# Group_G.net
KiCad netlist of a schematic drawn in EAGLE
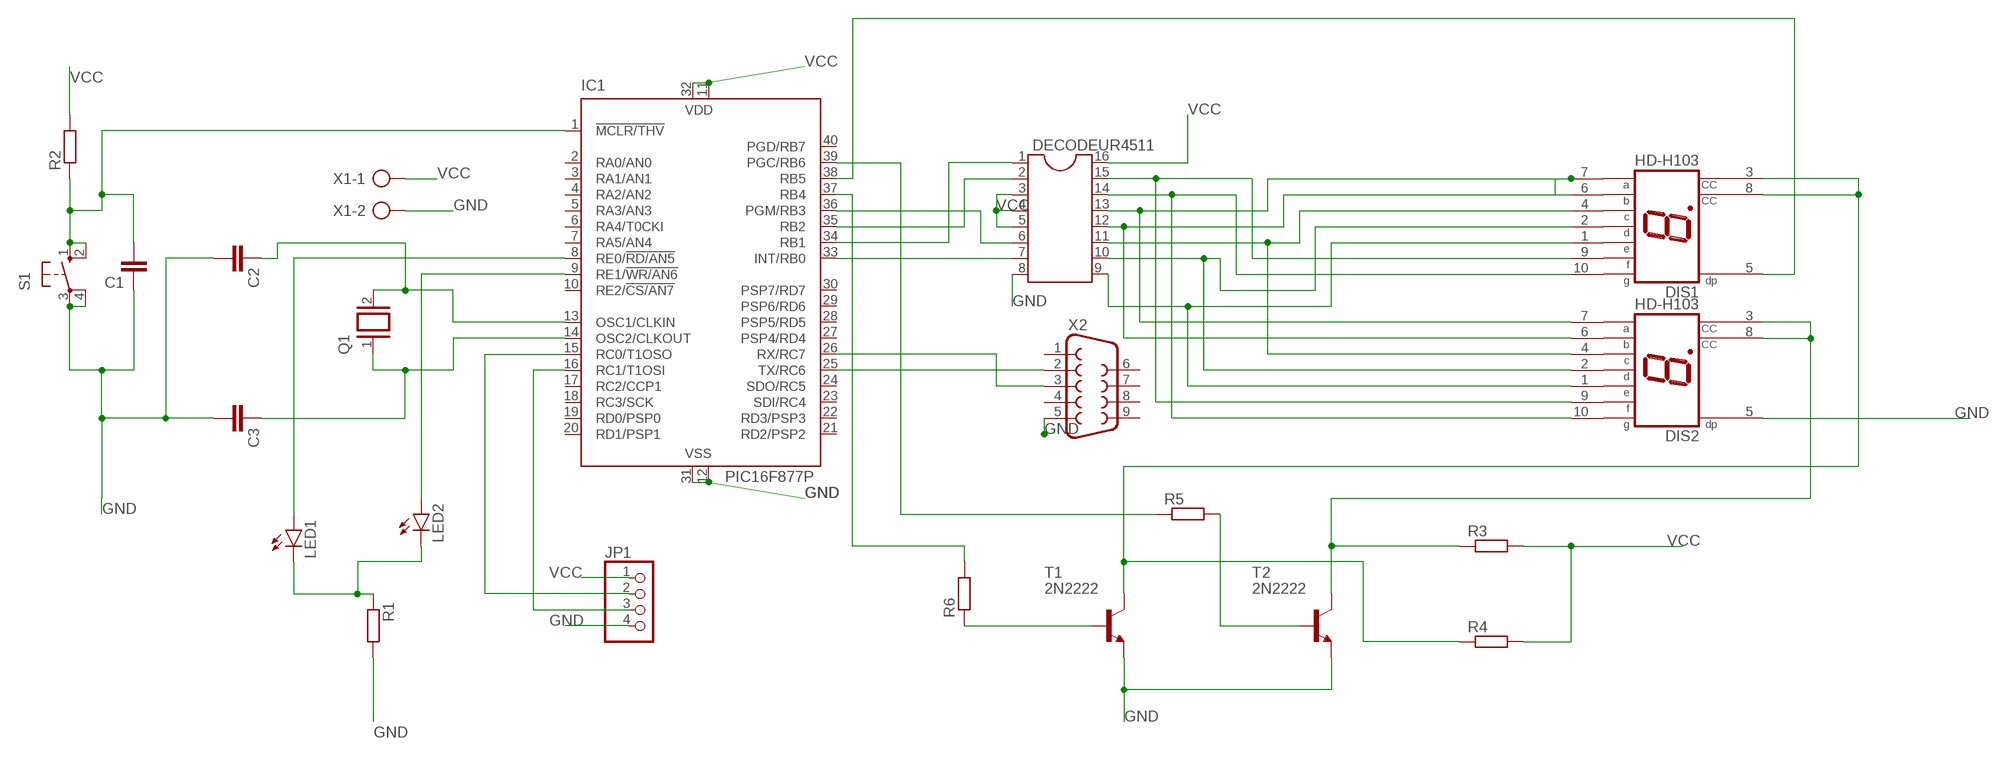
[diagram p0: schematic, sheet 1]

(export (version "E")
  (design (tool "Eeschema 10.0.6"))
  (components
    (comp (ref "C1")
      (value "C-EU025-025X050")
      (footprint "eagle-import:C025-025X050")
      (libsource (lib "eagle-import") (part "C-EU025-025X050"))
    )
    (comp (ref "C2")
      (value "C-EU025-025X050")
      (footprint "eagle-import:C025-025X050")
      (libsource (lib "eagle-import") (part "C-EU025-025X050"))
    )
    (comp (ref "C3")
      (value "C-EU025-025X050")
      (footprint "eagle-import:C025-025X050")
      (libsource (lib "eagle-import") (part "C-EU025-025X050"))
    )
    (comp (ref "DECODEUR4511")
      (value "DIL16")
      (footprint "eagle-import:DIL16")
      (libsource (lib "eagle-import") (part "DIL16"))
    )
    (comp (ref "DIS1")
      (value "HD-H103")
      (footprint "eagle-import:HDSP-M")
      (libsource (lib "eagle-import") (part "HD-H103"))
    )
    (comp (ref "DIS2")
      (value "HD-H103")
      (footprint "eagle-import:HDSP-M")
      (libsource (lib "eagle-import") (part "HD-H103"))
    )
    (comp (ref "IC1")
      (value "PIC16F877P")
      (footprint "eagle-import:DIL40")
      (fields (field (name "MF") "MICROCHIP") (field (name "MPN") "PIC16F877-04/P"))
      (libsource (lib "eagle-import") (part "PIC16F87P7"))
    )
    (comp (ref "JP1")
      (value "PINHD-1X4")
      (footprint "eagle-import:1X04")
      (libsource (lib "eagle-import") (part "PINHD-1X4"))
    )
    (comp (ref "LED1")
      (value "LED5MM")
      (footprint "eagle-import:LED5MM")
      (libsource (lib "eagle-import") (part "LED5MM"))
    )
    (comp (ref "LED2")
      (value "LED5MM")
      (footprint "eagle-import:LED5MM")
      (libsource (lib "eagle-import") (part "LED5MM"))
    )
    (comp (ref "Q1")
      (value "XTAL/S")
      (footprint "eagle-import:QS")
      (libsource (lib "eagle-import") (part "XTAL/S"))
    )
    (comp (ref "R1")
      (value "R-EU_0207/10")
      (footprint "eagle-import:0207_10")
      (libsource (lib "eagle-import") (part "R-EU_0207/10"))
    )
    (comp (ref "R2")
      (value "R-EU_0207/10")
      (footprint "eagle-import:0207_10")
      (libsource (lib "eagle-import") (part "R-EU_0207/10"))
    )
    (comp (ref "R3")
      (value "R-EU_0207/10")
      (footprint "eagle-import:0207_10")
      (libsource (lib "eagle-import") (part "R-EU_0207/10"))
    )
    (comp (ref "R4")
      (value "R-EU_0207/10")
      (footprint "eagle-import:0207_10")
      (libsource (lib "eagle-import") (part "R-EU_0207/10"))
    )
    (comp (ref "R5")
      (value "R-EU_0207/10")
      (footprint "eagle-import:0207_10")
      (libsource (lib "eagle-import") (part "R-EU_0207/10"))
    )
    (comp (ref "R6")
      (value "R-EU_0207/10")
      (footprint "eagle-import:0207_10")
      (libsource (lib "eagle-import") (part "R-EU_0207/10"))
    )
    (comp (ref "S1")
      (value "10-XX")
      (footprint "eagle-import:B3F-10XX")
      (fields (field (name "MPN") "B3F-1000"))
      (libsource (lib "eagle-import") (part "10-XX"))
    )
    (comp (ref "T1")
      (value "2N2222")
      (footprint "eagle-import:TO18")
      (libsource (lib "eagle-import") (part "2N2222"))
    )
    (comp (ref "T2")
      (value "2N2222")
      (footprint "eagle-import:TO18")
      (libsource (lib "eagle-import") (part "2N2222"))
    )
    (comp (ref "X1")
      (value "AK300/2")
      (footprint "eagle-import:AK300_2")
      (libsource (lib "eagle-import") (part "AK300/2"))
    )
    (comp (ref "X2")
      (value "F09H")
      (footprint "eagle-import:F09H")
      (libsource (lib "eagle-import") (part "F09H"))
    )
  )
  (nets
    (net (code "1") (name "/GND") (class "Default")
      (node (ref "C1") (pin "1") (pinfunction "1_1") (pintype "passive"))
      (node (ref "C2") (pin "2") (pinfunction "2_2") (pintype "passive"))
      (node (ref "C3") (pin "2") (pinfunction "2_2") (pintype "passive"))
      (node (ref "DECODEUR4511") (pin "8") (pinfunction "8_8") (pintype "passive"))
      (node (ref "DIS2") (pin "5") (pinfunction "DP_5") (pintype "passive"))
      (node (ref "IC1") (pin "12") (pinfunction "VSS_12") (pintype "power_in"))
      (node (ref "IC1") (pin "31") (pinfunction "VSS_31") (pintype "power_in"))
      (node (ref "JP1") (pin "4") (pinfunction "4_4") (pintype "passive"))
      (node (ref "R1") (pin "2") (pinfunction "2_2") (pintype "passive"))
      (node (ref "S1") (pin "3") (pinfunction "P_3") (pintype "passive"))
      (node (ref "S1") (pin "4") (pinfunction "P1_4") (pintype "passive"))
      (node (ref "T1") (pin "1") (pinfunction "E_1") (pintype "passive"))
      (node (ref "T2") (pin "1") (pinfunction "E_1") (pintype "passive"))
      (node (ref "X1") (pin "2") (pinfunction "KL_2") (pintype "passive"))
      (node (ref "X2") (pin "5") (pinfunction "5_5") (pintype "passive"))
    )
    (net (code "2") (name "/VCC") (class "Default")
      (node (ref "DECODEUR4511") (pin "16") (pinfunction "16_16") (pintype "passive"))
      (node (ref "DECODEUR4511") (pin "3") (pinfunction "3_3") (pintype "passive"))
      (node (ref "DECODEUR4511") (pin "4") (pinfunction "4_4") (pintype "passive"))
      (node (ref "DECODEUR4511") (pin "5") (pinfunction "5_5") (pintype "passive"))
      (node (ref "IC1") (pin "11") (pinfunction "VDD_11") (pintype "power_in"))
      (node (ref "IC1") (pin "32") (pinfunction "VDD_32") (pintype "power_in"))
      (node (ref "JP1") (pin "1") (pinfunction "1_1") (pintype "passive"))
      (node (ref "R2") (pin "2") (pinfunction "2_2") (pintype "passive"))
      (node (ref "R3") (pin "2") (pinfunction "2_2") (pintype "passive"))
      (node (ref "R4") (pin "2") (pinfunction "2_2") (pintype "passive"))
      (node (ref "X1") (pin "1") (pinfunction "KL_1") (pintype "passive"))
    )
    (net (code "3") (name "Net-(DIS1-A)") (class "Default")
      (node (ref "DECODEUR4511") (pin "13") (pinfunction "13_13") (pintype "passive"))
      (node (ref "DIS1") (pin "7") (pinfunction "A_7") (pintype "passive"))
      (node (ref "DIS2") (pin "7") (pinfunction "A_7") (pintype "passive"))
    )
    (net (code "4") (name "Net-(DIS1-B)") (class "Default")
      (node (ref "DECODEUR4511") (pin "12") (pinfunction "12_12") (pintype "passive"))
      (node (ref "DIS1") (pin "6") (pinfunction "B_6") (pintype "passive"))
      (node (ref "DIS2") (pin "6") (pinfunction "B_6") (pintype "passive"))
    )
    (net (code "5") (name "Net-(DIS1-C)") (class "Default")
      (node (ref "DECODEUR4511") (pin "11") (pinfunction "11_11") (pintype "passive"))
      (node (ref "DIS1") (pin "4") (pinfunction "C_4") (pintype "passive"))
      (node (ref "DIS2") (pin "4") (pinfunction "C_4") (pintype "passive"))
    )
    (net (code "6") (name "Net-(DIS1-D)") (class "Default")
      (node (ref "DECODEUR4511") (pin "10") (pinfunction "10_10") (pintype "passive"))
      (node (ref "DIS1") (pin "2") (pinfunction "D_2") (pintype "passive"))
      (node (ref "DIS2") (pin "2") (pinfunction "D_2") (pintype "passive"))
    )
    (net (code "7") (name "Net-(DIS1-DP)") (class "Default")
      (node (ref "DIS1") (pin "5") (pinfunction "DP_5") (pintype "passive"))
      (node (ref "IC1") (pin "38") (pinfunction "RB5_38") (pintype "bidirectional"))
    )
    (net (code "8") (name "Net-(DIS1-E)") (class "Default")
      (node (ref "DECODEUR4511") (pin "9") (pinfunction "9_9") (pintype "passive"))
      (node (ref "DIS1") (pin "1") (pinfunction "E_1") (pintype "passive"))
      (node (ref "DIS2") (pin "1") (pinfunction "E_1") (pintype "passive"))
    )
    (net (code "9") (name "Net-(DIS1-F)") (class "Default")
      (node (ref "DECODEUR4511") (pin "15") (pinfunction "15_15") (pintype "passive"))
      (node (ref "DIS1") (pin "9") (pinfunction "F_9") (pintype "passive"))
      (node (ref "DIS2") (pin "9") (pinfunction "F_9") (pintype "passive"))
    )
    (net (code "10") (name "Net-(DIS1-G)") (class "Default")
      (node (ref "DECODEUR4511") (pin "14") (pinfunction "14_14") (pintype "passive"))
      (node (ref "DIS1") (pin "10") (pinfunction "G_10") (pintype "passive"))
      (node (ref "DIS2") (pin "10") (pinfunction "G_10") (pintype "passive"))
    )
    (net (code "11") (name "Net-(IC1-INT{slash}RB0)") (class "Default")
      (node (ref "DECODEUR4511") (pin "7") (pinfunction "7_7") (pintype "passive"))
      (node (ref "IC1") (pin "33") (pinfunction "INT/RB0_33") (pintype "bidirectional"))
    )
    (net (code "12") (name "Net-(IC1-OSC1{slash}CLKIN)") (class "Default")
      (node (ref "C2") (pin "1") (pinfunction "1_1") (pintype "passive"))
      (node (ref "IC1") (pin "13") (pinfunction "OSC1/CLKIN_13") (pintype "input"))
      (node (ref "Q1") (pin "2") (pinfunction "2_2") (pintype "passive"))
    )
    (net (code "13") (name "Net-(IC1-OSC2{slash}CLKOUT)") (class "Default")
      (node (ref "C3") (pin "1") (pinfunction "1_1") (pintype "passive"))
      (node (ref "IC1") (pin "14") (pinfunction "OSC2/CLKOUT_14") (pintype "output"))
      (node (ref "Q1") (pin "1") (pinfunction "1_1") (pintype "passive"))
    )
    (net (code "14") (name "Net-(IC1-PGC{slash}RB6)") (class "Default")
      (node (ref "IC1") (pin "39") (pinfunction "PGC/RB6_39") (pintype "bidirectional"))
      (node (ref "R5") (pin "1") (pinfunction "1_1") (pintype "passive"))
    )
    (net (code "15") (name "Net-(IC1-PGM{slash}RB3)") (class "Default")
      (node (ref "DECODEUR4511") (pin "6") (pinfunction "6_6") (pintype "passive"))
      (node (ref "IC1") (pin "36") (pinfunction "PGM/RB3_36") (pintype "bidirectional"))
    )
    (net (code "16") (name "Net-(IC1-RB1)") (class "Default")
      (node (ref "DECODEUR4511") (pin "1") (pinfunction "1_1") (pintype "passive"))
      (node (ref "IC1") (pin "34") (pinfunction "RB1_34") (pintype "bidirectional"))
    )
    (net (code "17") (name "Net-(IC1-RB2)") (class "Default")
      (node (ref "DECODEUR4511") (pin "2") (pinfunction "2_2") (pintype "passive"))
      (node (ref "IC1") (pin "35") (pinfunction "RB2_35") (pintype "bidirectional"))
    )
    (net (code "18") (name "Net-(IC1-RB4)") (class "Default")
      (node (ref "IC1") (pin "37") (pinfunction "RB4_37") (pintype "bidirectional"))
      (node (ref "R6") (pin "2") (pinfunction "2_2") (pintype "passive"))
    )
    (net (code "19") (name "Net-(IC1-RC0{slash}T1OSO)") (class "Default")
      (node (ref "IC1") (pin "15") (pinfunction "RC0/T1OSO_15") (pintype "bidirectional"))
      (node (ref "JP1") (pin "2") (pinfunction "2_2") (pintype "passive"))
    )
    (net (code "20") (name "Net-(IC1-RC1{slash}T1OSI)") (class "Default")
      (node (ref "IC1") (pin "16") (pinfunction "RC1/T1OSI_16") (pintype "bidirectional"))
      (node (ref "JP1") (pin "3") (pinfunction "3_3") (pintype "passive"))
    )
    (net (code "21") (name "Net-(IC1-RE0{slash}~{RD{slash}AN5})") (class "Default")
      (node (ref "IC1") (pin "8") (pinfunction "RE0/~{RD/AN5}_8") (pintype "bidirectional"))
      (node (ref "LED1") (pin "A") (pinfunction "A_A") (pintype "passive"))
    )
    (net (code "22") (name "Net-(IC1-RE1{slash}~{WR{slash}AN6})") (class "Default")
      (node (ref "IC1") (pin "9") (pinfunction "RE1/~{WR/AN6}_9") (pintype "bidirectional"))
      (node (ref "LED2") (pin "A") (pinfunction "A_A") (pintype "passive"))
    )
    (net (code "23") (name "Net-(IC1-RX{slash}RC7)") (class "Default")
      (node (ref "IC1") (pin "26") (pinfunction "RX/RC7_26") (pintype "bidirectional"))
      (node (ref "X2") (pin "3") (pinfunction "3_3") (pintype "passive"))
    )
    (net (code "24") (name "Net-(IC1-TX{slash}RC6)") (class "Default")
      (node (ref "IC1") (pin "25") (pinfunction "TX/RC6_25") (pintype "bidirectional"))
      (node (ref "X2") (pin "2") (pinfunction "2_2") (pintype "passive"))
    )
    (net (code "25") (name "Net-(IC1-~{MCLR{slash}THV})") (class "Default")
      (node (ref "C1") (pin "2") (pinfunction "2_2") (pintype "passive"))
      (node (ref "IC1") (pin "1") (pinfunction "~{MCLR/THV}_1") (pintype "input"))
      (node (ref "R2") (pin "1") (pinfunction "1_1") (pintype "passive"))
      (node (ref "S1") (pin "1") (pinfunction "S_1") (pintype "passive"))
      (node (ref "S1") (pin "2") (pinfunction "S1_2") (pintype "passive"))
    )
    (net (code "26") (name "Net-(LED1-C)") (class "Default")
      (node (ref "LED1") (pin "K") (pinfunction "C_K") (pintype "passive"))
      (node (ref "LED2") (pin "K") (pinfunction "C_K") (pintype "passive"))
      (node (ref "R1") (pin "1") (pinfunction "1_1") (pintype "passive"))
    )
    (net (code "27") (name "Net-(T1-B)") (class "Default")
      (node (ref "R6") (pin "1") (pinfunction "1_1") (pintype "passive"))
      (node (ref "T1") (pin "2") (pinfunction "B_2") (pintype "passive"))
    )
    (net (code "28") (name "Net-(T1-C)") (class "Default")
      (node (ref "DIS1") (pin "3") (pinfunction "CC_3") (pintype "passive"))
      (node (ref "DIS1") (pin "8") (pinfunction "CC_8") (pintype "passive"))
      (node (ref "R4") (pin "1") (pinfunction "1_1") (pintype "passive"))
      (node (ref "T1") (pin "3") (pinfunction "C_3") (pintype "passive"))
    )
    (net (code "29") (name "Net-(T2-B)") (class "Default")
      (node (ref "R5") (pin "2") (pinfunction "2_2") (pintype "passive"))
      (node (ref "T2") (pin "2") (pinfunction "B_2") (pintype "passive"))
    )
    (net (code "30") (name "Net-(T2-C)") (class "Default")
      (node (ref "DIS2") (pin "3") (pinfunction "CC_3") (pintype "passive"))
      (node (ref "DIS2") (pin "8") (pinfunction "CC_8") (pintype "passive"))
      (node (ref "R3") (pin "1") (pinfunction "1_1") (pintype "passive"))
      (node (ref "T2") (pin "3") (pinfunction "C_3") (pintype "passive"))
    )
    (net (code "31") (name "unconnected-(IC1-PGD{slash}RB7-Pad40)") (class "Default")
      (node (ref "IC1") (pin "40") (pinfunction "PGD/RB7_40") (pintype "bidirectional"))
    )
    (net (code "32") (name "unconnected-(IC1-PSP4{slash}RD4-Pad27)") (class "Default")
      (node (ref "IC1") (pin "27") (pinfunction "PSP4/RD4_27") (pintype "bidirectional"))
    )
    (net (code "33") (name "unconnected-(IC1-PSP5{slash}RD5-Pad28)") (class "Default")
      (node (ref "IC1") (pin "28") (pinfunction "PSP5/RD5_28") (pintype "bidirectional"))
    )
    (net (code "34") (name "unconnected-(IC1-PSP6{slash}RD6-Pad29)") (class "Default")
      (node (ref "IC1") (pin "29") (pinfunction "PSP6/RD6_29") (pintype "bidirectional"))
    )
    (net (code "35") (name "unconnected-(IC1-PSP7{slash}RD7-Pad30)") (class "Default")
      (node (ref "IC1") (pin "30") (pinfunction "PSP7/RD7_30") (pintype "bidirectional"))
    )
    (net (code "36") (name "unconnected-(IC1-RA0{slash}AN0-Pad2)") (class "Default")
      (node (ref "IC1") (pin "2") (pinfunction "RA0/AN0_2") (pintype "bidirectional"))
    )
    (net (code "37") (name "unconnected-(IC1-RA1{slash}AN1-Pad3)") (class "Default")
      (node (ref "IC1") (pin "3") (pinfunction "RA1/AN1_3") (pintype "bidirectional"))
    )
    (net (code "38") (name "unconnected-(IC1-RA2{slash}AN2-Pad4)") (class "Default")
      (node (ref "IC1") (pin "4") (pinfunction "RA2/AN2_4") (pintype "bidirectional"))
    )
    (net (code "39") (name "unconnected-(IC1-RA3{slash}AN3-Pad5)") (class "Default")
      (node (ref "IC1") (pin "5") (pinfunction "RA3/AN3_5") (pintype "bidirectional"))
    )
    (net (code "40") (name "unconnected-(IC1-RA4{slash}T0CKI-Pad6)") (class "Default")
      (node (ref "IC1") (pin "6") (pinfunction "RA4/T0CKI_6") (pintype "bidirectional"))
    )
    (net (code "41") (name "unconnected-(IC1-RA5{slash}AN4-Pad7)") (class "Default")
      (node (ref "IC1") (pin "7") (pinfunction "RA5/AN4_7") (pintype "bidirectional"))
    )
    (net (code "42") (name "unconnected-(IC1-RC2{slash}CCP1-Pad17)") (class "Default")
      (node (ref "IC1") (pin "17") (pinfunction "RC2/CCP1_17") (pintype "bidirectional"))
    )
    (net (code "43") (name "unconnected-(IC1-RC3{slash}SCK-Pad18)") (class "Default")
      (node (ref "IC1") (pin "18") (pinfunction "RC3/SCK_18") (pintype "bidirectional"))
    )
    (net (code "44") (name "unconnected-(IC1-RD0{slash}PSP0-Pad19)") (class "Default")
      (node (ref "IC1") (pin "19") (pinfunction "RD0/PSP0_19") (pintype "bidirectional"))
    )
    (net (code "45") (name "unconnected-(IC1-RD1{slash}PSP1-Pad20)") (class "Default")
      (node (ref "IC1") (pin "20") (pinfunction "RD1/PSP1_20") (pintype "bidirectional"))
    )
    (net (code "46") (name "unconnected-(IC1-RD2{slash}PSP2-Pad21)") (class "Default")
      (node (ref "IC1") (pin "21") (pinfunction "RD2/PSP2_21") (pintype "bidirectional"))
    )
    (net (code "47") (name "unconnected-(IC1-RD3{slash}PSP3-Pad22)") (class "Default")
      (node (ref "IC1") (pin "22") (pinfunction "RD3/PSP3_22") (pintype "bidirectional"))
    )
    (net (code "48") (name "unconnected-(IC1-RE2{slash}~{CS{slash}AN7}-Pad10)") (class "Default")
      (node (ref "IC1") (pin "10") (pinfunction "RE2/~{CS/AN7}_10") (pintype "bidirectional"))
    )
    (net (code "49") (name "unconnected-(IC1-SDI{slash}RC4-Pad23)") (class "Default")
      (node (ref "IC1") (pin "23") (pinfunction "SDI/RC4_23") (pintype "bidirectional"))
    )
    (net (code "50") (name "unconnected-(IC1-SDO{slash}RC5-Pad24)") (class "Default")
      (node (ref "IC1") (pin "24") (pinfunction "SDO/RC5_24") (pintype "bidirectional"))
    )
    (net (code "51") (name "unconnected-(X2-Pad1)") (class "Default")
      (node (ref "X2") (pin "1") (pinfunction "1_1") (pintype "passive"))
    )
    (net (code "52") (name "unconnected-(X2-Pad4)") (class "Default")
      (node (ref "X2") (pin "4") (pinfunction "4_4") (pintype "passive"))
    )
    (net (code "53") (name "unconnected-(X2-Pad6)") (class "Default")
      (node (ref "X2") (pin "6") (pinfunction "6_6") (pintype "passive"))
    )
    (net (code "54") (name "unconnected-(X2-Pad7)") (class "Default")
      (node (ref "X2") (pin "7") (pinfunction "7_7") (pintype "passive"))
    )
    (net (code "55") (name "unconnected-(X2-Pad8)") (class "Default")
      (node (ref "X2") (pin "8") (pinfunction "8_8") (pintype "passive"))
    )
    (net (code "56") (name "unconnected-(X2-Pad9)") (class "Default")
      (node (ref "X2") (pin "9") (pinfunction "9_9") (pintype "passive"))
    )
  )
)
